# positioningAndThermistor.net
KiCad netlist of a schematic drawn in Altium Designer
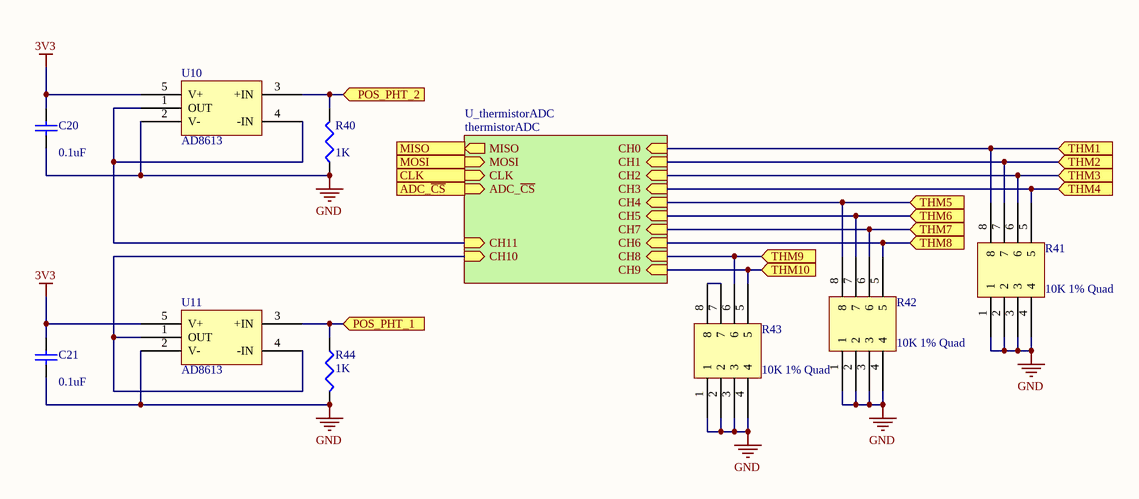
[diagram p0: positioningAndThermistor.SchDoc]

(export (version "E")
  (design (tool "Eeschema 10.0.6"))
  (components
    (comp (ref "C20")
      (value "0.1uF")
      (footprint "0402")
      (description "Capacitor (Semiconductor SIM Model)")
      (fields (field (name "PUBLISHER") "Altium Limited"))
      (libsource (lib "Miscellaneous Devices") (part "Cap Semi"))
    )
    (comp (ref "C21")
      (value "0.1uF")
      (footprint "0402")
      (description "Capacitor (Semiconductor SIM Model)")
      (fields (field (name "PUBLISHER") "Altium Limited"))
      (libsource (lib "Miscellaneous Devices") (part "Cap Semi"))
    )
    (comp (ref "R40")
      (value "1K")
      (footprint "J1-0603")
      (description "Resistor")
      (fields (field (name "PUBLISHER") "Altium Limited"))
      (libsource (lib "Miscellaneous Devices") (part "Res3"))
    )
    (comp (ref "R41")
      (value "10K 1% Quad")
      (description "Quad pack resistor")
      (libsource (lib "PAY") (part "Res Quad Pack"))
    )
    (comp (ref "R42")
      (value "10K 1% Quad")
      (description "Quad pack resistor")
      (libsource (lib "PAY") (part "Res Quad Pack"))
    )
    (comp (ref "R43")
      (value "10K 1% Quad")
      (description "Quad pack resistor")
      (libsource (lib "PAY") (part "Res Quad Pack"))
    )
    (comp (ref "R44")
      (value "1K")
      (footprint "J1-0603")
      (description "Resistor")
      (fields (field (name "PUBLISHER") "Altium Limited"))
      (libsource (lib "Miscellaneous Devices") (part "Res3"))
    )
    (comp (ref "U10")
      (value "AD8613")
      (footprint "SOP-65P200X125-5N")
      (description "Low power, low noise rail-to-rail op-amp.")
      (libsource (lib "PAY") (part "AD8613"))
    )
    (comp (ref "U11")
      (value "AD8613")
      (footprint "SOP-65P200X125-5N")
      (description "Low power, low noise rail-to-rail op-amp.")
      (libsource (lib "PAY") (part "AD8613"))
    )
  )
  (nets
    (net (code "2") (name "/CH10") (class "Default")
      (node (ref "U11") (pin "1") (pinfunction "OUT_1") (pintype "passive"))
      (node (ref "U11") (pin "4") (pinfunction "-IN_4") (pintype "passive"))
    )
    (net (code "3") (name "/CH11") (class "Default")
      (node (ref "U10") (pin "1") (pinfunction "OUT_1") (pintype "passive"))
      (node (ref "U10") (pin "4") (pinfunction "-IN_4") (pintype "passive"))
    )
    (net (code "7") (name "/POS_PHT_1") (class "Default")
      (node (ref "R44") (pin "1") (pinfunction "1_1") (pintype "passive"))
      (node (ref "U11") (pin "3") (pinfunction "+IN_3") (pintype "passive"))
    )
    (net (code "8") (name "/POS_PHT_2") (class "Default")
      (node (ref "R40") (pin "2") (pinfunction "2_2") (pintype "passive"))
      (node (ref "U10") (pin "3") (pinfunction "+IN_3") (pintype "passive"))
    )
    (net (code "9") (name "/THM1") (class "Default")
      (node (ref "R41") (pin "8") (pinfunction "8_8") (pintype "passive"))
    )
    (net (code "10") (name "/THM2") (class "Default")
      (node (ref "R41") (pin "7") (pinfunction "7_7") (pintype "passive"))
    )
    (net (code "11") (name "/THM3") (class "Default")
      (node (ref "R41") (pin "6") (pinfunction "6_6") (pintype "passive"))
    )
    (net (code "12") (name "/THM4") (class "Default")
      (node (ref "R41") (pin "5") (pinfunction "5_5") (pintype "passive"))
    )
    (net (code "13") (name "/THM5") (class "Default")
      (node (ref "R42") (pin "8") (pinfunction "8_8") (pintype "passive"))
    )
    (net (code "14") (name "/THM6") (class "Default")
      (node (ref "R42") (pin "7") (pinfunction "7_7") (pintype "passive"))
    )
    (net (code "15") (name "/THM7") (class "Default")
      (node (ref "R42") (pin "6") (pinfunction "6_6") (pintype "passive"))
    )
    (net (code "16") (name "/THM8") (class "Default")
      (node (ref "R42") (pin "5") (pinfunction "5_5") (pintype "passive"))
    )
    (net (code "17") (name "/THM9") (class "Default")
      (node (ref "R43") (pin "6") (pinfunction "6_6") (pintype "passive"))
    )
    (net (code "18") (name "/THM10") (class "Default")
      (node (ref "R43") (pin "5") (pinfunction "5_5") (pintype "passive"))
    )
    (net (code "19") (name "3V3") (class "Default")
      (node (ref "C20") (pin "2") (pinfunction "2_2") (pintype "passive"))
      (node (ref "C21") (pin "2") (pinfunction "2_2") (pintype "passive"))
      (node (ref "U10") (pin "5") (pinfunction "V+_5") (pintype "passive"))
      (node (ref "U11") (pin "5") (pinfunction "V+_5") (pintype "passive"))
    )
    (net (code "20") (name "GND") (class "Default")
      (node (ref "C20") (pin "1") (pinfunction "1_1") (pintype "passive"))
      (node (ref "C21") (pin "1") (pinfunction "1_1") (pintype "passive"))
      (node (ref "R40") (pin "1") (pinfunction "1_1") (pintype "passive"))
      (node (ref "R41") (pin "1") (pinfunction "1_1") (pintype "passive"))
      (node (ref "R41") (pin "2") (pinfunction "2_2") (pintype "passive"))
      (node (ref "R41") (pin "3") (pinfunction "3_3") (pintype "passive"))
      (node (ref "R41") (pin "4") (pinfunction "4_4") (pintype "passive"))
      (node (ref "R42") (pin "1") (pinfunction "1_1") (pintype "passive"))
      (node (ref "R42") (pin "2") (pinfunction "2_2") (pintype "passive"))
      (node (ref "R42") (pin "3") (pinfunction "3_3") (pintype "passive"))
      (node (ref "R42") (pin "4") (pinfunction "4_4") (pintype "passive"))
      (node (ref "R43") (pin "1") (pinfunction "1_1") (pintype "passive"))
      (node (ref "R43") (pin "2") (pinfunction "2_2") (pintype "passive"))
      (node (ref "R43") (pin "3") (pinfunction "3_3") (pintype "passive"))
      (node (ref "R43") (pin "4") (pinfunction "4_4") (pintype "passive"))
      (node (ref "R44") (pin "2") (pinfunction "2_2") (pintype "passive"))
      (node (ref "U10") (pin "2") (pinfunction "V-_2") (pintype "passive"))
      (node (ref "U11") (pin "2") (pinfunction "V-_2") (pintype "passive"))
    )
    (net (code "21") (name "Net-(R43-Pad7)") (class "Default")
      (node (ref "R43") (pin "7") (pinfunction "7_7") (pintype "passive"))
      (node (ref "R43") (pin "8") (pinfunction "8_8") (pintype "passive"))
    )
  )
)
